# p2c-000-plain.net
KiCad netlist of a schematic drawn in EAGLE
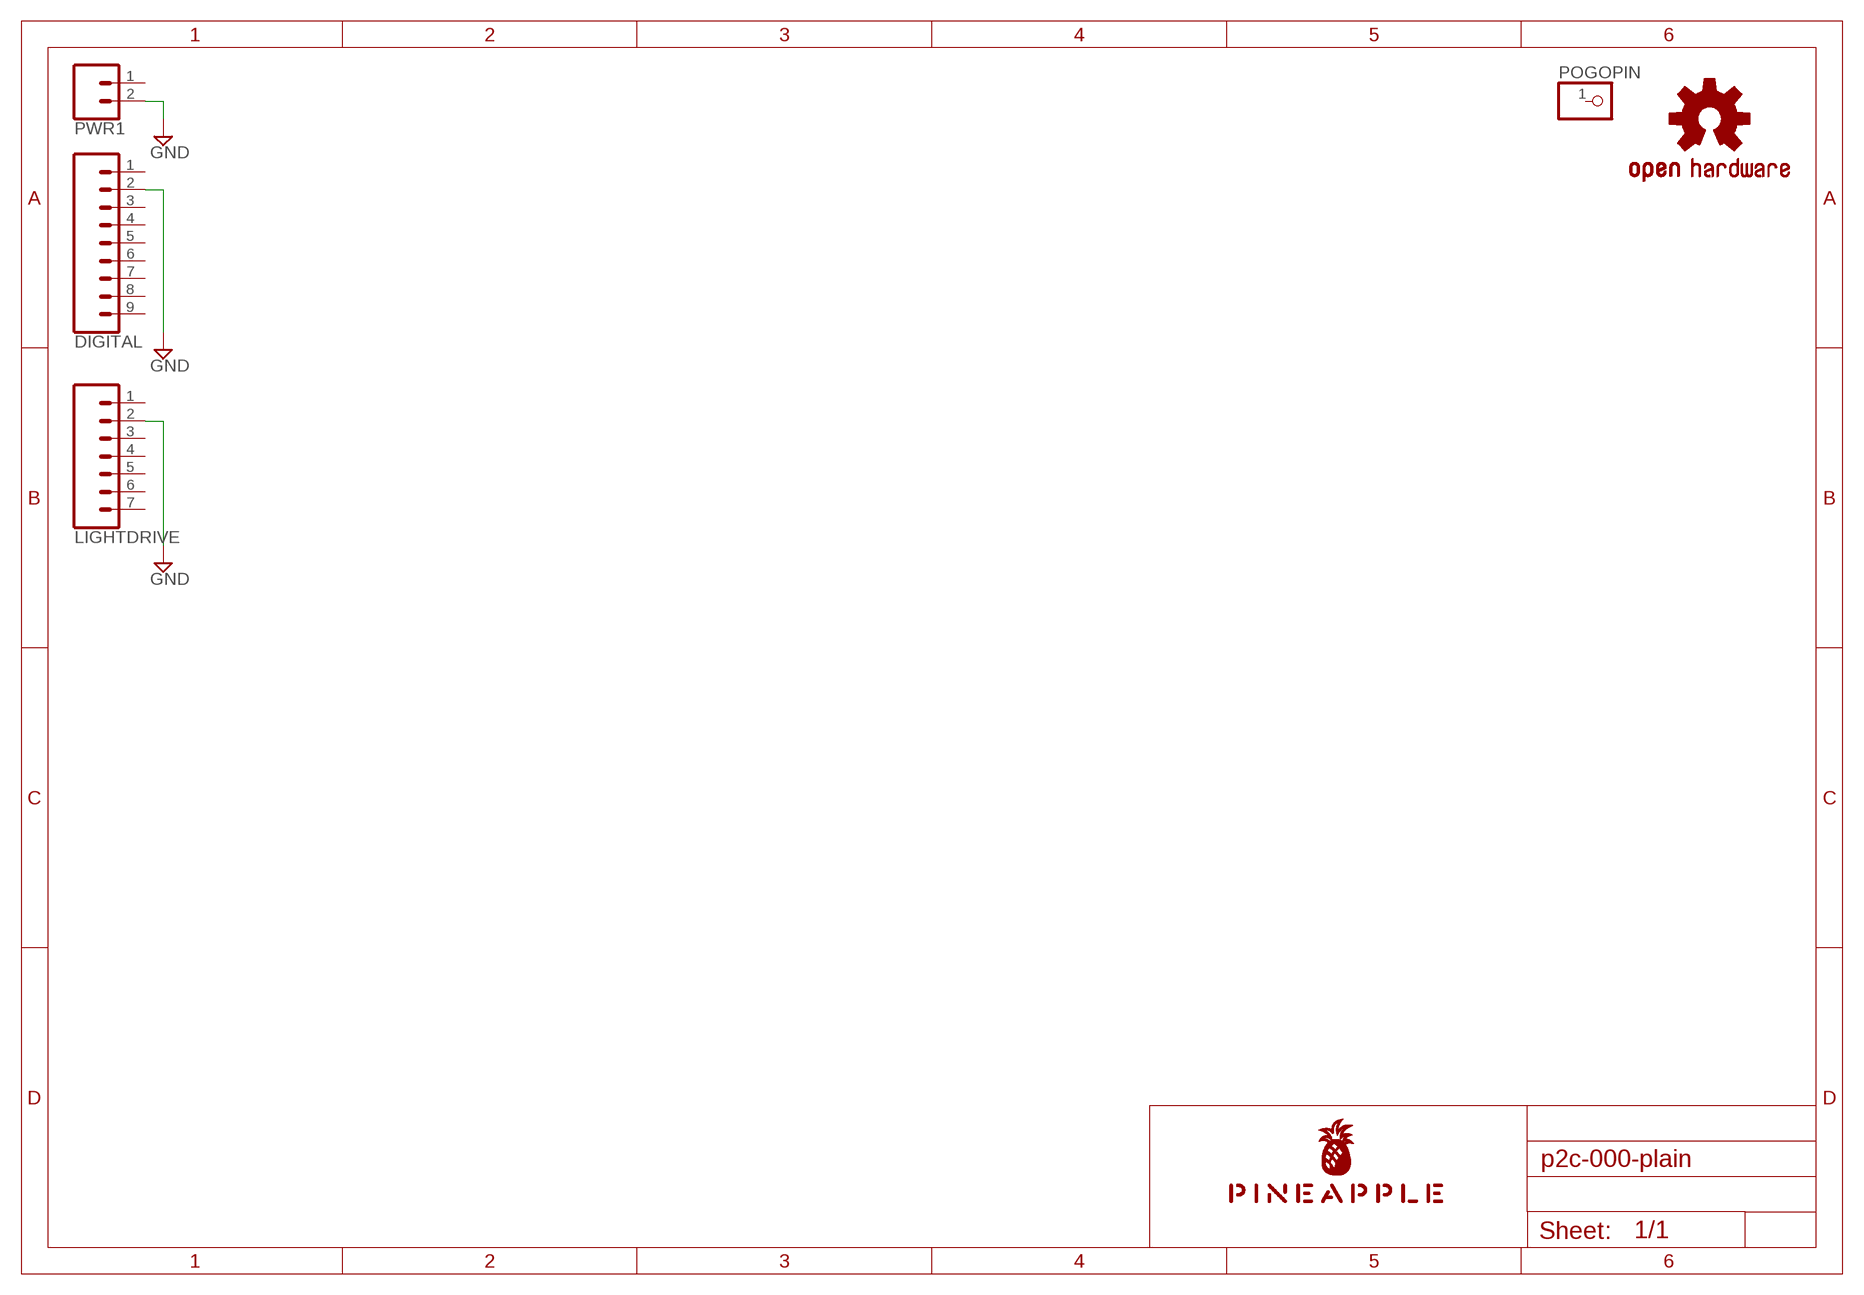
[diagram p0: schematic, sheet 1]

(export (version "E")
  (design (tool "Eeschema 10.0.6"))
  (components
    (comp (ref "DIGITAL")
      (value "CONN_09")
      (footprint "eagle-import:1X09")
      (libsource (lib "eagle-import") (part "CONN_09"))
    )
    (comp (ref "LIGHTDRIVE")
      (value "CONN_07")
      (footprint "eagle-import:1X07")
      (libsource (lib "eagle-import") (part "CONN_07"))
    )
    (comp (ref "LOGO1")
      (value "OSHW-LOGOS-COPPER")
      (footprint "eagle-import:OSHW-LOGO-S_COPPER")
      (libsource (lib "eagle-import") (part "OSHW-LOGOS-COPPER"))
    )
    (comp (ref "POGOPIN")
      (value "PINHD-1X1")
      (footprint "eagle-import:1X01")
      (libsource (lib "eagle-import") (part "PINHD-1X1"))
    )
    (comp (ref "PWR1")
      (value "CONN_02")
      (footprint "eagle-import:1X02")
      (libsource (lib "eagle-import") (part "CONN_02"))
    )
    (comp (ref "U$1")
      (value "PINEAPPLE450_SILK")
      (footprint "eagle-import:PINEAPPLE450_SILK")
      (libsource (lib "eagle-import") (part "PINEAPPLE450_SILK"))
    )
  )
  (nets
    (net (code "1") (name "GND") (class "Default")
      (node (ref "DIGITAL") (pin "2") (pinfunction "2_2") (pintype "passive"))
      (node (ref "LIGHTDRIVE") (pin "2") (pinfunction "2_2") (pintype "passive"))
      (node (ref "PWR1") (pin "2") (pinfunction "2_2") (pintype "passive"))
    )
    (net (code "2") (name "unconnected-(DIGITAL-Pad1)") (class "Default")
      (node (ref "DIGITAL") (pin "1") (pinfunction "1_1") (pintype "passive"))
    )
    (net (code "3") (name "unconnected-(DIGITAL-Pad3)") (class "Default")
      (node (ref "DIGITAL") (pin "3") (pinfunction "3_3") (pintype "passive"))
    )
    (net (code "4") (name "unconnected-(DIGITAL-Pad4)") (class "Default")
      (node (ref "DIGITAL") (pin "4") (pinfunction "4_4") (pintype "passive"))
    )
    (net (code "5") (name "unconnected-(DIGITAL-Pad5)") (class "Default")
      (node (ref "DIGITAL") (pin "5") (pinfunction "5_5") (pintype "passive"))
    )
    (net (code "6") (name "unconnected-(DIGITAL-Pad6)") (class "Default")
      (node (ref "DIGITAL") (pin "6") (pinfunction "6_6") (pintype "passive"))
    )
    (net (code "7") (name "unconnected-(DIGITAL-Pad7)") (class "Default")
      (node (ref "DIGITAL") (pin "7") (pinfunction "7_7") (pintype "passive"))
    )
    (net (code "8") (name "unconnected-(DIGITAL-Pad8)") (class "Default")
      (node (ref "DIGITAL") (pin "8") (pinfunction "8_8") (pintype "passive"))
    )
    (net (code "9") (name "unconnected-(DIGITAL-Pad9)") (class "Default")
      (node (ref "DIGITAL") (pin "9") (pinfunction "9_9") (pintype "passive"))
    )
    (net (code "10") (name "unconnected-(LIGHTDRIVE-Pad1)") (class "Default")
      (node (ref "LIGHTDRIVE") (pin "1") (pinfunction "1_1") (pintype "passive"))
    )
    (net (code "11") (name "unconnected-(LIGHTDRIVE-Pad3)") (class "Default")
      (node (ref "LIGHTDRIVE") (pin "3") (pinfunction "3_3") (pintype "passive"))
    )
    (net (code "12") (name "unconnected-(LIGHTDRIVE-Pad4)") (class "Default")
      (node (ref "LIGHTDRIVE") (pin "4") (pinfunction "4_4") (pintype "passive"))
    )
    (net (code "13") (name "unconnected-(LIGHTDRIVE-Pad5)") (class "Default")
      (node (ref "LIGHTDRIVE") (pin "5") (pinfunction "5_5") (pintype "passive"))
    )
    (net (code "14") (name "unconnected-(LIGHTDRIVE-Pad6)") (class "Default")
      (node (ref "LIGHTDRIVE") (pin "6") (pinfunction "6_6") (pintype "passive"))
    )
    (net (code "15") (name "unconnected-(LIGHTDRIVE-Pad7)") (class "Default")
      (node (ref "LIGHTDRIVE") (pin "7") (pinfunction "7_7") (pintype "passive"))
    )
    (net (code "16") (name "unconnected-(POGOPIN-Pad1)") (class "Default")
      (node (ref "POGOPIN") (pin "1") (pinfunction "1_1") (pintype "passive"))
    )
    (net (code "17") (name "unconnected-(PWR1-Pad1)") (class "Default")
      (node (ref "PWR1") (pin "1") (pinfunction "1_1") (pintype "passive"))
    )
  )
)
